# AND_OR.net
KiCad netlist of a schematic drawn in EAGLE
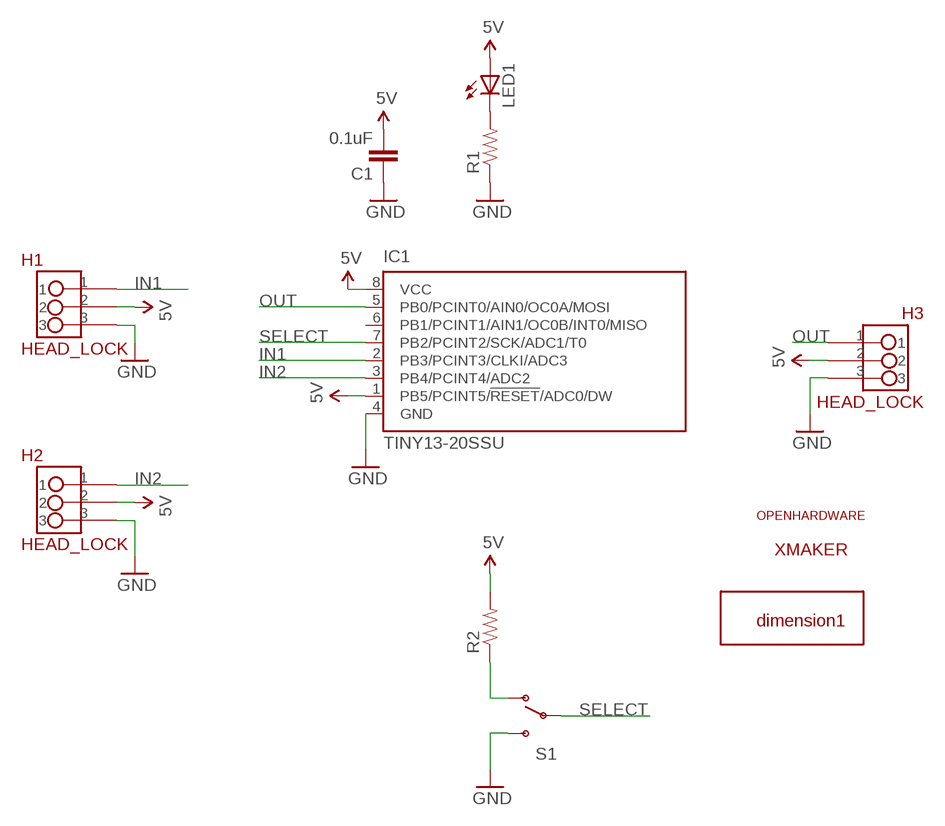
[diagram p0: schematic, sheet 1]

(export (version "E")
  (design (tool "Eeschema 10.0.6"))
  (components
    (comp (ref "C1")
      (value "0.1uF")
      (footprint "eagle-import:0603-CAP")
      (libsource (lib "eagle-import") (part "0.1UF-25V(+80/-20%)(0603)"))
    )
    (comp (ref "H1")
      (value "HEAD_LOCK")
      (footprint "eagle-import:HEAD_LOCK")
      (libsource (lib "eagle-import") (part "HEAD_LOCK"))
    )
    (comp (ref "H2")
      (value "HEAD_LOCK")
      (footprint "eagle-import:HEAD_LOCK")
      (libsource (lib "eagle-import") (part "HEAD_LOCK"))
    )
    (comp (ref "H3")
      (value "HEAD_LOCK")
      (footprint "eagle-import:HEAD_LOCK")
      (libsource (lib "eagle-import") (part "HEAD_LOCK"))
    )
    (comp (ref "IC1")
      (value "TINY13-20SSU")
      (footprint "eagle-import:8S1")
      (fields (field (name "MPN") "ATTINY13-20SSU"))
      (libsource (lib "eagle-import") (part "TINY13SSU-20"))
    )
    (comp (ref "LED1")
      (value "LEDSML0603")
      (footprint "eagle-import:SML0603")
      (libsource (lib "eagle-import") (part "LEDSML0603"))
    )
    (comp (ref "R1")
      (value "RESISTOR0603-RES")
      (footprint "eagle-import:0603-RES")
      (libsource (lib "eagle-import") (part "RESISTOR0603-RES"))
    )
    (comp (ref "R2")
      (value "RESISTOR0603-RES")
      (footprint "eagle-import:0603-RES")
      (libsource (lib "eagle-import") (part "RESISTOR0603-RES"))
    )
    (comp (ref "S1")
      (value "SWITCH-SPDTKIT")
      (footprint "eagle-import:SWITCH-SPDT_KIT")
      (libsource (lib "eagle-import") (part "SWITCH-SPDTKIT"))
    )
    (comp (ref "U$2")
      (value "XMAKERLOGO2")
      (footprint "eagle-import:XMAKERLOGO2")
      (libsource (lib "eagle-import") (part "XMAKERLOGO2"))
    )
    (comp (ref "U$3")
      (value "DIMENSION1")
      (footprint "eagle-import:DIMENSION1")
      (libsource (lib "eagle-import") (part "DIMENSION1"))
    )
    (comp (ref "U$4")
      (value "OPENHARDWARE")
      (footprint "eagle-import:OPENHARDWARE")
      (libsource (lib "eagle-import") (part "OPENHARDWARE"))
    )
  )
  (nets
    (net (code "1") (name "/IN1") (class "Default")
      (node (ref "H1") (pin "1") (pinfunction "1_1") (pintype "passive"))
      (node (ref "IC1") (pin "2") (pinfunction "PB3/PCINT3/CLKI/ADC3_2") (pintype "bidirectional"))
    )
    (net (code "2") (name "/IN2") (class "Default")
      (node (ref "H2") (pin "1") (pinfunction "1_1") (pintype "passive"))
      (node (ref "IC1") (pin "3") (pinfunction "PB4/PCINT4/ADC2_3") (pintype "bidirectional"))
    )
    (net (code "3") (name "/OUT") (class "Default")
      (node (ref "H3") (pin "1") (pinfunction "1_1") (pintype "passive"))
      (node (ref "IC1") (pin "5") (pinfunction "PB0/PCINT0/AIN0/OC0A/MOSI_5") (pintype "bidirectional"))
    )
    (net (code "4") (name "/SELECT") (class "Default")
      (node (ref "IC1") (pin "7") (pinfunction "PB2/PCINT2/SCK/ADC1/T0_7") (pintype "bidirectional"))
      (node (ref "S1") (pin "2") (pinfunction "P_2") (pintype "passive"))
    )
    (net (code "5") (name "5V") (class "Default")
      (node (ref "C1") (pin "2") (pinfunction "2_2") (pintype "passive"))
      (node (ref "H1") (pin "2") (pinfunction "2_2") (pintype "passive"))
      (node (ref "H2") (pin "2") (pinfunction "2_2") (pintype "passive"))
      (node (ref "H3") (pin "2") (pinfunction "2_2") (pintype "passive"))
      (node (ref "IC1") (pin "1") (pinfunction "PB5/PCINT5/~{RESET}/ADC0/DW_1") (pintype "bidirectional"))
      (node (ref "IC1") (pin "8") (pinfunction "VCC_8") (pintype "power_in"))
      (node (ref "LED1") (pin "A") (pinfunction "A_A") (pintype "passive"))
      (node (ref "R2") (pin "2") (pinfunction "2_2") (pintype "passive"))
    )
    (net (code "6") (name "GND") (class "Default")
      (node (ref "C1") (pin "1") (pinfunction "1_1") (pintype "passive"))
      (node (ref "H1") (pin "3") (pinfunction "3_3") (pintype "passive"))
      (node (ref "H2") (pin "3") (pinfunction "3_3") (pintype "passive"))
      (node (ref "H3") (pin "3") (pinfunction "3_3") (pintype "passive"))
      (node (ref "IC1") (pin "4") (pinfunction "GND_4") (pintype "power_in"))
      (node (ref "R1") (pin "1") (pinfunction "1_1") (pintype "passive"))
      (node (ref "S1") (pin "3") (pinfunction "S_3") (pintype "passive"))
    )
    (net (code "7") (name "Net-(LED1-PadC)") (class "Default")
      (node (ref "LED1") (pin "C") (pinfunction "C_C") (pintype "passive"))
      (node (ref "R1") (pin "2") (pinfunction "2_2") (pintype "passive"))
    )
    (net (code "8") (name "Net-(S1-O)") (class "Default")
      (node (ref "R2") (pin "1") (pinfunction "1_1") (pintype "passive"))
      (node (ref "S1") (pin "1") (pinfunction "O_1") (pintype "passive"))
    )
    (net (code "9") (name "unconnected-(IC1-PB1{slash}PCINT1{slash}AIN1{slash}OC0B{slash}INT0{slash}MISO-Pad6)") (class "Default")
      (node (ref "IC1") (pin "6") (pinfunction "PB1/PCINT1/AIN1/OC0B/INT0/MISO_6") (pintype "bidirectional"))
    )
  )
)
